# ORD_FV1_1.net
KiCad netlist of a schematic drawn in Altium Designer
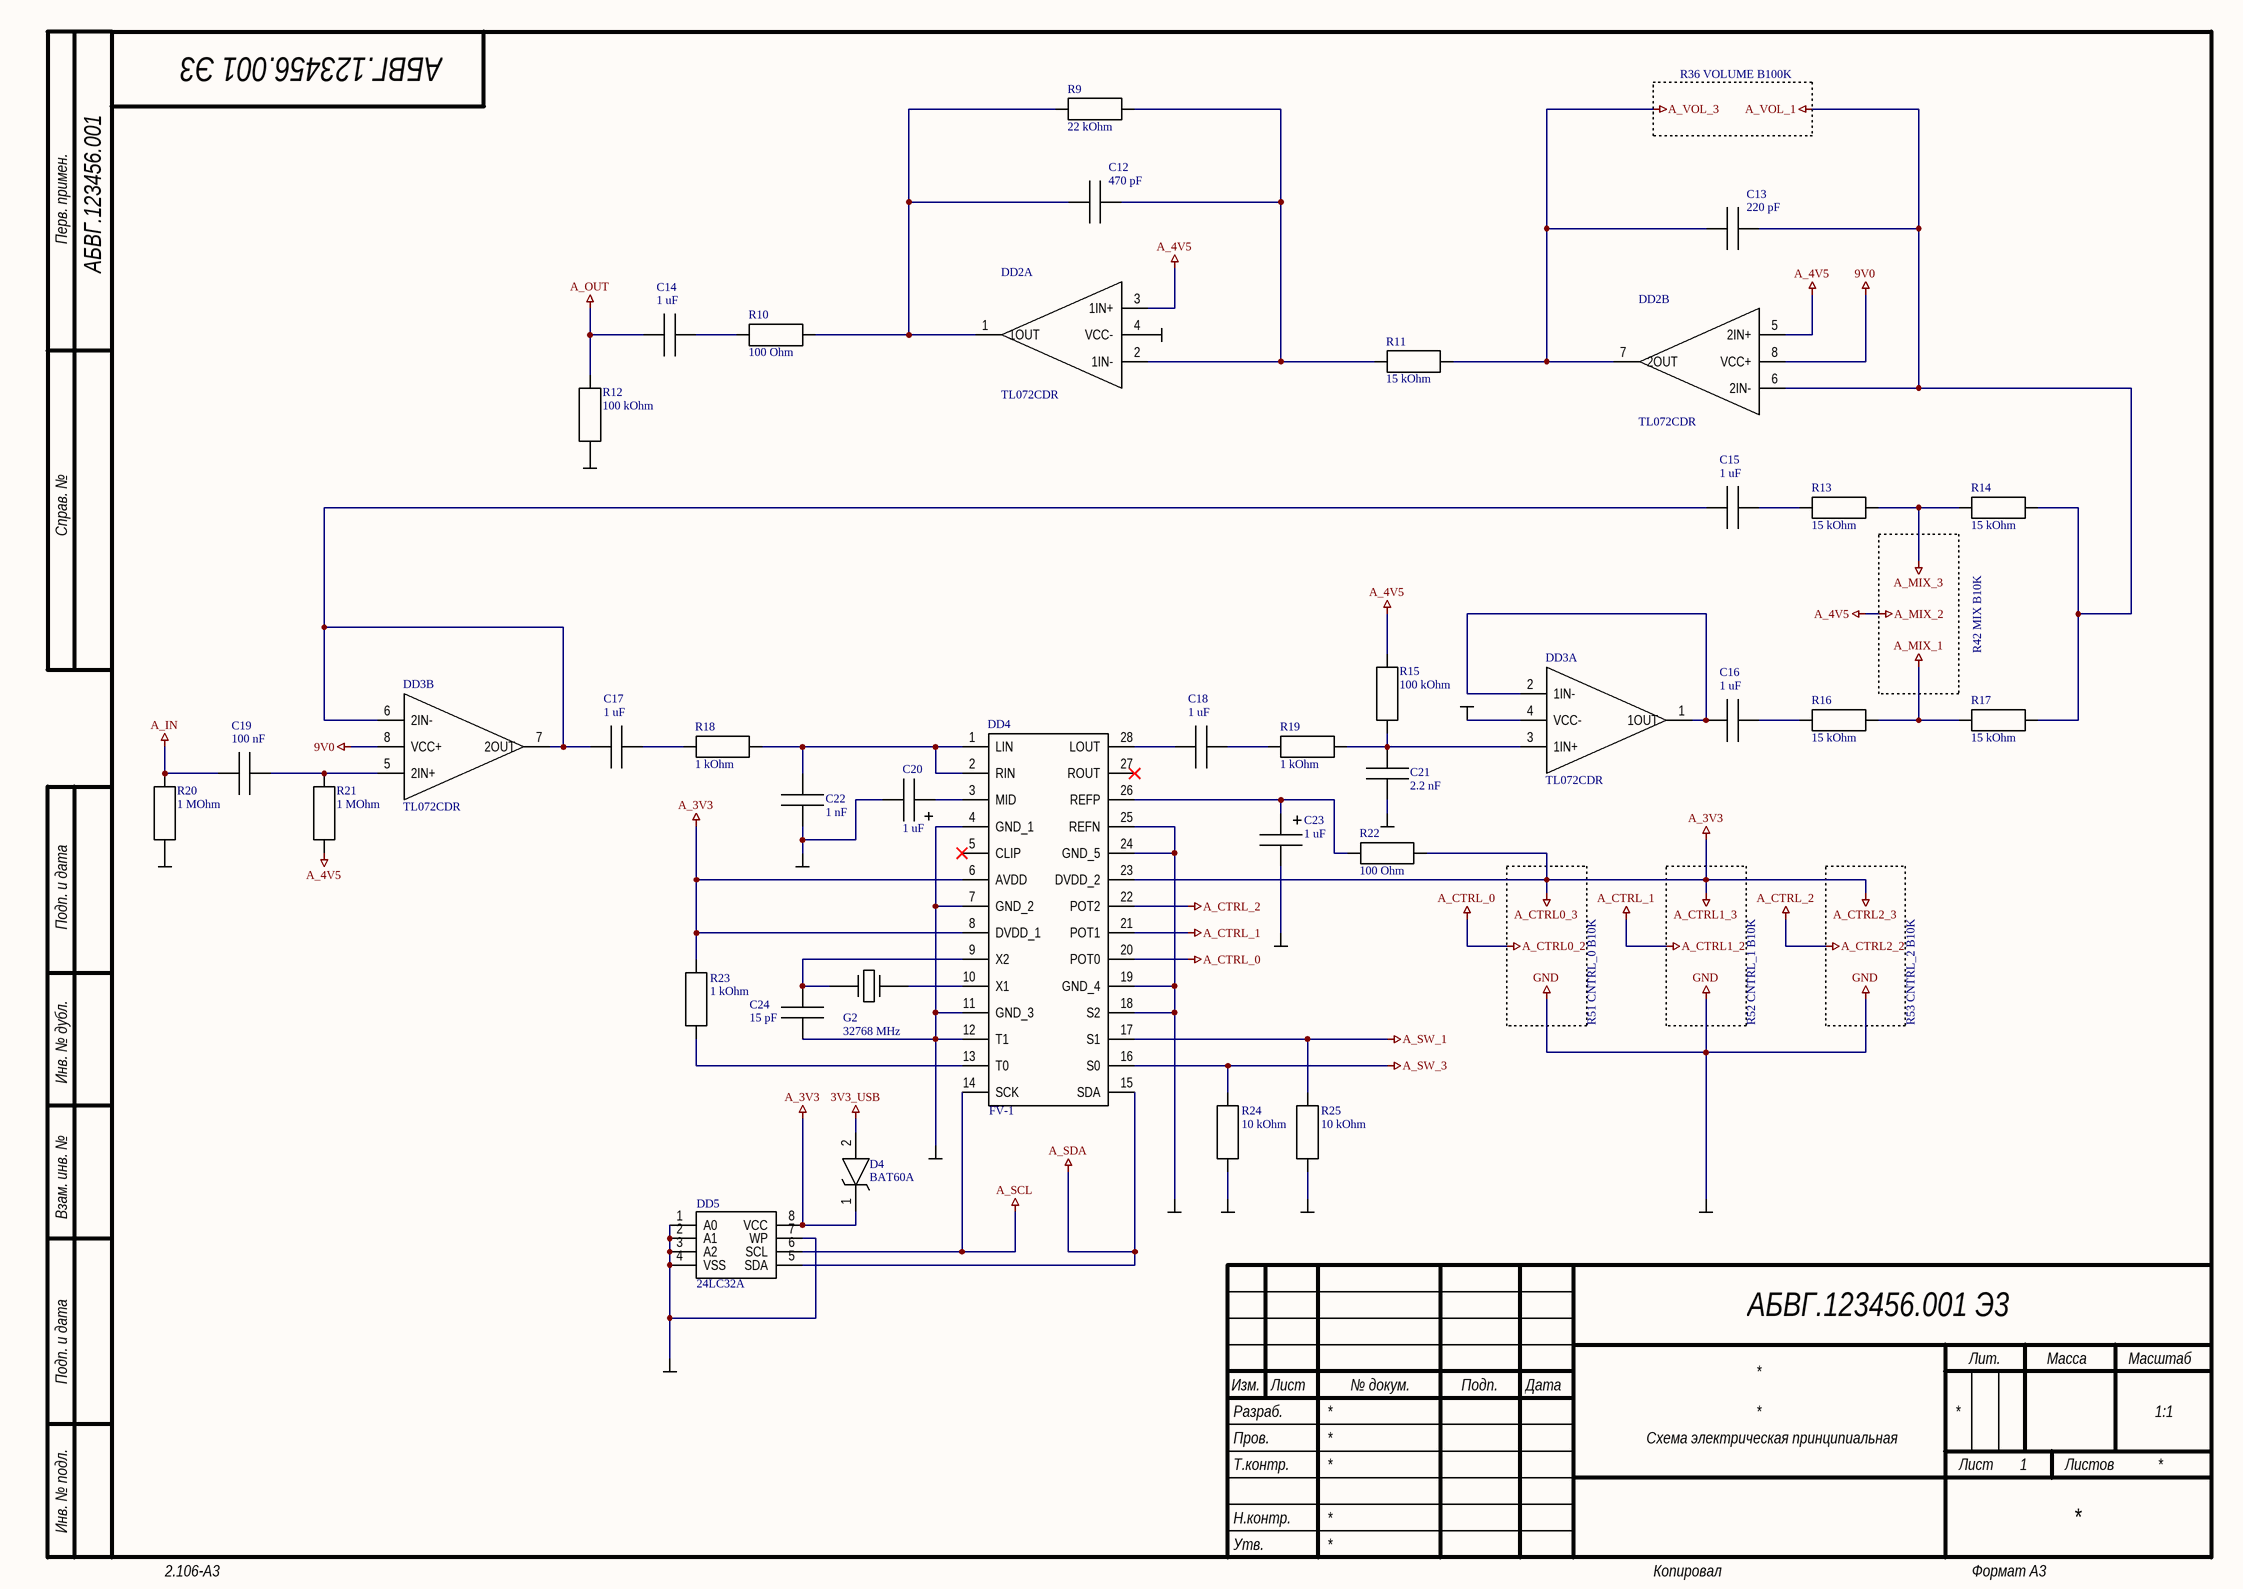
[diagram p0: ORD_FV1_1.SchDoc]

(export (version "E")
  (design (tool "Eeschema 10.0.6"))
  (components
    (comp (ref "C12")
      (value "470 pF")
      (footprint "C0805[2012]")
      (libsource (lib "Gost_passive_lib") (part "Capacitor"))
    )
    (comp (ref "C13")
      (value "220 pF")
      (footprint "C0805[2012]")
      (libsource (lib "Gost_passive_lib") (part "Capacitor"))
    )
    (comp (ref "C14")
      (value "1 uF")
      (footprint "C0805[2012]")
      (libsource (lib "Gost_passive_lib") (part "Capacitor"))
    )
    (comp (ref "C15")
      (value "1 uF")
      (footprint "C0805[2012]")
      (libsource (lib "Gost_passive_lib") (part "Capacitor"))
    )
    (comp (ref "C16")
      (value "1 uF")
      (footprint "C0805[2012]")
      (libsource (lib "Gost_passive_lib") (part "Capacitor"))
    )
    (comp (ref "C17")
      (value "1 uF")
      (footprint "C0805[2012]")
      (libsource (lib "Gost_passive_lib") (part "Capacitor"))
    )
    (comp (ref "C18")
      (value "1 uF")
      (footprint "C0805[2012]")
      (libsource (lib "Gost_passive_lib") (part "Capacitor"))
    )
    (comp (ref "C19")
      (value "100 nF")
      (footprint "C0805[2012]")
      (libsource (lib "Gost_passive_lib") (part "Capacitor"))
    )
    (comp (ref "C20")
      (value "1 uF")
      (footprint "C3216_CASE-A")
      (libsource (lib "Gost_passive_lib") (part "Capacitor_Pol"))
    )
    (comp (ref "C21")
      (value "2.2 nF")
      (footprint "C0805[2012]")
      (libsource (lib "Gost_passive_lib") (part "Capacitor"))
    )
    (comp (ref "C22")
      (value "1 nF")
      (footprint "C0805[2012]")
      (libsource (lib "Gost_passive_lib") (part "Capacitor"))
    )
    (comp (ref "C23")
      (value "1 uF")
      (footprint "C3216_CASE-A")
      (libsource (lib "Gost_passive_lib") (part "Capacitor_Pol"))
    )
    (comp (ref "C24")
      (value "15 pF")
      (footprint "C0805[2012]")
      (libsource (lib "Gost_passive_lib") (part "Capacitor"))
    )
    (comp (ref "D4")
      (value "BAT60A")
      (footprint "SOD323")
      (description "Diode Schottky 10V 3A Automotive 2-Pin SOD-323 T/R")
      (libsource (lib "Gost_passive_lib") (part "BAT60A"))
    )
    (comp (ref "DD2")
      (value "TL072CDR")
      (footprint "SO8")
      (description "TL072CDR, Dual Operational Amplifier 4 MHz -18 to 18V, 8-Pin SO")
      (fields
        (field (name "MANUFACTURER_PART_NUMBER") "LM358DT")
        (field (name "MOUSER PART NUMBER") "511-LM358DT")
      )
      (libsource (lib "Gost_active_libs") (part "TL072CDR"))
    )
    (comp (ref "DD3")
      (value "TL072CDR")
      (footprint "SO8")
      (description "TL072CDR, Dual Operational Amplifier 4 MHz -18 to 18V, 8-Pin SO")
      (fields
        (field (name "MANUFACTURER_PART_NUMBER") "LM358DT")
        (field (name "MOUSER PART NUMBER") "511-LM358DT")
      )
      (libsource (lib "Gost_active_libs") (part "TL072CDR"))
    )
    (comp (ref "DD4")
      (value "FV-1")
      (footprint "SOIC28")
      (description "FV-1 Reverb IC, Integrated Stereo ADC & DAC, Integrated Circuit, SOIC-28 300 MIL")
      (fields (field (name "MANUFACTURER_PART_NUMBER") "FV-1 Reverb IC"))
      (libsource (lib "Gost_active_libs") (part "FV-1"))
    )
    (comp (ref "DD5")
      (value "24LC32A")
      (footprint "DIP8_WITH_SOCKET")
      (description "32K I2C Serial EEPROM with Quarter-Array Write-Protect")
      (fields
        (field (name "MANUFACTURER_PART_NUMBER") "24LC32AF-I/P")
        (field (name "MOUSER PART NUMBER") "579-24LC32AF-I/P")
      )
      (libsource (lib "Gost_active_libs") (part "24LC32A"))
    )
    (comp (ref "G2")
      (value "32768 MHz")
      (footprint "HC-49")
      (libsource (lib "Gost_passive_lib") (part "Crystal_2pin"))
    )
    (comp (ref "R9")
      (value "22 kOhm")
      (footprint "R0805[2012]")
      (libsource (lib "Gost_passive_lib") (part "Resistor"))
    )
    (comp (ref "R10")
      (value "100 Ohm")
      (footprint "R0805[2012]")
      (libsource (lib "Gost_passive_lib") (part "Resistor"))
    )
    (comp (ref "R11")
      (value "15 kOhm")
      (footprint "R0805[2012]")
      (libsource (lib "Gost_passive_lib") (part "Resistor"))
    )
    (comp (ref "R12")
      (value "100 kOhm")
      (footprint "R0805[2012]")
      (libsource (lib "Gost_passive_lib") (part "Resistor"))
    )
    (comp (ref "R13")
      (value "15 kOhm")
      (footprint "R0805[2012]")
      (libsource (lib "Gost_passive_lib") (part "Resistor"))
    )
    (comp (ref "R14")
      (value "15 kOhm")
      (footprint "R0805[2012]")
      (libsource (lib "Gost_passive_lib") (part "Resistor"))
    )
    (comp (ref "R15")
      (value "100 kOhm")
      (footprint "R0805[2012]")
      (libsource (lib "Gost_passive_lib") (part "Resistor"))
    )
    (comp (ref "R16")
      (value "15 kOhm")
      (footprint "R0805[2012]")
      (libsource (lib "Gost_passive_lib") (part "Resistor"))
    )
    (comp (ref "R17")
      (value "15 kOhm")
      (footprint "R0805[2012]")
      (libsource (lib "Gost_passive_lib") (part "Resistor"))
    )
    (comp (ref "R18")
      (value "1 kOhm")
      (footprint "R0805[2012]")
      (libsource (lib "Gost_passive_lib") (part "Resistor"))
    )
    (comp (ref "R19")
      (value "1 kOhm")
      (footprint "R0805[2012]")
      (libsource (lib "Gost_passive_lib") (part "Resistor"))
    )
    (comp (ref "R20")
      (value "1 MOhm")
      (footprint "R0805[2012]")
      (libsource (lib "Gost_passive_lib") (part "Resistor"))
    )
    (comp (ref "R21")
      (value "1 MOhm")
      (footprint "R0805[2012]")
      (libsource (lib "Gost_passive_lib") (part "Resistor"))
    )
    (comp (ref "R22")
      (value "100 Ohm")
      (footprint "R0805[2012]")
      (libsource (lib "Gost_passive_lib") (part "Resistor"))
    )
    (comp (ref "R23")
      (value "1 kOhm")
      (footprint "R0805[2012]")
      (libsource (lib "Gost_passive_lib") (part "Resistor"))
    )
    (comp (ref "R24")
      (value "10 kOhm")
      (footprint "R0805[2012]")
      (libsource (lib "Gost_passive_lib") (part "Resistor"))
    )
    (comp (ref "R25")
      (value "10 kOhm")
      (footprint "R0805[2012]")
      (libsource (lib "Gost_passive_lib") (part "Resistor"))
    )
  )
  (nets
    (net (code "1") (name "3V3_USB") (class "Default")
      (node (ref "D4") (pin "2") (pinfunction "A_2") (pintype "passive"))
    )
    (net (code "2") (name "9V0") (class "Default")
      (node (ref "DD2") (pin "8") (pinfunction "VCC+_8") (pintype "power_in"))
      (node (ref "DD3") (pin "8") (pinfunction "VCC+_8") (pintype "power_in"))
    )
    (net (code "3") (name "A_3V3") (class "Default")
      (node (ref "D4") (pin "1") (pinfunction "K_1") (pintype "passive"))
      (node (ref "DD4") (pin "23") (pinfunction "DVDD_2_23") (pintype "passive"))
      (node (ref "DD4") (pin "6") (pinfunction "AVDD_6") (pintype "passive"))
      (node (ref "DD4") (pin "8") (pinfunction "DVDD_1_8") (pintype "passive"))
      (node (ref "DD5") (pin "8") (pinfunction "VCC_8") (pintype "passive"))
      (node (ref "R22") (pin "1") (pinfunction "1_1") (pintype "passive"))
      (node (ref "R23") (pin "2") (pinfunction "2_2") (pintype "passive"))
    )
    (net (code "4") (name "A_4V5") (class "Default")
      (node (ref "DD2") (pin "3") (pinfunction "1IN+_3") (pintype "passive"))
      (node (ref "DD2") (pin "5") (pinfunction "2IN+_5") (pintype "passive"))
      (node (ref "R15") (pin "1") (pinfunction "1_1") (pintype "passive"))
      (node (ref "R21") (pin "1") (pinfunction "1_1") (pintype "passive"))
    )
    (net (code "5") (name "A_CTRL0_2") (class "Default")
      (node (ref "DD4") (pin "20") (pinfunction "POT0_20") (pintype "passive"))
    )
    (net (code "6") (name "A_CTRL1_2") (class "Default")
      (node (ref "DD4") (pin "21") (pinfunction "POT1_21") (pintype "passive"))
    )
    (net (code "7") (name "A_CTRL2_2") (class "Default")
      (node (ref "DD4") (pin "22") (pinfunction "POT2_22") (pintype "passive"))
    )
    (net (code "8") (name "A_IN") (class "Default")
      (node (ref "C19") (pin "1") (pinfunction "1_1") (pintype "passive"))
      (node (ref "R20") (pin "2") (pinfunction "2_2") (pintype "passive"))
    )
    (net (code "9") (name "A_MIX_1") (class "Default")
      (node (ref "R16") (pin "1") (pinfunction "1_1") (pintype "passive"))
      (node (ref "R17") (pin "2") (pinfunction "2_2") (pintype "passive"))
    )
    (net (code "10") (name "A_MIX_3") (class "Default")
      (node (ref "R13") (pin "1") (pinfunction "1_1") (pintype "passive"))
      (node (ref "R14") (pin "2") (pinfunction "2_2") (pintype "passive"))
    )
    (net (code "11") (name "A_OUT") (class "Default")
      (node (ref "C14") (pin "1") (pinfunction "1_1") (pintype "passive"))
      (node (ref "R12") (pin "2") (pinfunction "2_2") (pintype "passive"))
    )
    (net (code "12") (name "A_SCL") (class "Default")
      (node (ref "DD4") (pin "14") (pinfunction "SCK_14") (pintype "passive"))
      (node (ref "DD5") (pin "6") (pinfunction "SCL_6") (pintype "passive"))
    )
    (net (code "13") (name "A_SDA") (class "Default")
      (node (ref "DD4") (pin "15") (pinfunction "SDA_15") (pintype "passive"))
      (node (ref "DD5") (pin "5") (pinfunction "SDA_5") (pintype "passive"))
    )
    (net (code "14") (name "A_SW_1") (class "Default")
      (node (ref "DD4") (pin "17") (pinfunction "S1_17") (pintype "passive"))
      (node (ref "R25") (pin "2") (pinfunction "2_2") (pintype "passive"))
    )
    (net (code "15") (name "A_SW_3") (class "Default")
      (node (ref "DD4") (pin "16") (pinfunction "S0_16") (pintype "passive"))
      (node (ref "R24") (pin "2") (pinfunction "2_2") (pintype "passive"))
    )
    (net (code "16") (name "A_VOL_1") (class "Default")
      (node (ref "C13") (pin "2") (pinfunction "2_2") (pintype "passive"))
      (node (ref "DD2") (pin "6") (pinfunction "2IN-_6") (pintype "passive"))
      (node (ref "R14") (pin "1") (pinfunction "1_1") (pintype "passive"))
      (node (ref "R17") (pin "1") (pinfunction "1_1") (pintype "passive"))
    )
    (net (code "17") (name "A_VOL_3") (class "Default")
      (node (ref "C13") (pin "1") (pinfunction "1_1") (pintype "passive"))
      (node (ref "DD2") (pin "7") (pinfunction "2OUT_7") (pintype "passive"))
      (node (ref "R11") (pin "1") (pinfunction "1_1") (pintype "passive"))
    )
    (net (code "18") (name "GND") (class "Default")
      (node (ref "C20") (pin "2") (pinfunction "2_2") (pintype "passive"))
      (node (ref "C21") (pin "1") (pinfunction "1_1") (pintype "passive"))
      (node (ref "C22") (pin "1") (pinfunction "1_1") (pintype "passive"))
      (node (ref "C23") (pin "2") (pinfunction "2_2") (pintype "passive"))
      (node (ref "C24") (pin "2") (pinfunction "2_2") (pintype "passive"))
      (node (ref "DD2") (pin "4") (pinfunction "VCC-_4") (pintype "power_in"))
      (node (ref "DD3") (pin "4") (pinfunction "VCC-_4") (pintype "power_in"))
      (node (ref "DD4") (pin "11") (pinfunction "GND_3_11") (pintype "passive"))
      (node (ref "DD4") (pin "12") (pinfunction "T1_12") (pintype "passive"))
      (node (ref "DD4") (pin "18") (pinfunction "S2_18") (pintype "passive"))
      (node (ref "DD4") (pin "19") (pinfunction "GND_4_19") (pintype "passive"))
      (node (ref "DD4") (pin "24") (pinfunction "GND_5_24") (pintype "passive"))
      (node (ref "DD4") (pin "25") (pinfunction "REFN_25") (pintype "passive"))
      (node (ref "DD4") (pin "4") (pinfunction "GND_1_4") (pintype "passive"))
      (node (ref "DD4") (pin "7") (pinfunction "GND_2_7") (pintype "passive"))
      (node (ref "DD5") (pin "1") (pinfunction "A0_1") (pintype "passive"))
      (node (ref "DD5") (pin "2") (pinfunction "A1_2") (pintype "passive"))
      (node (ref "DD5") (pin "3") (pinfunction "A2_3") (pintype "passive"))
      (node (ref "DD5") (pin "4") (pinfunction "VSS_4") (pintype "passive"))
      (node (ref "DD5") (pin "7") (pinfunction "WP_7") (pintype "passive"))
      (node (ref "R12") (pin "1") (pinfunction "1_1") (pintype "passive"))
      (node (ref "R20") (pin "1") (pinfunction "1_1") (pintype "passive"))
      (node (ref "R24") (pin "1") (pinfunction "1_1") (pintype "passive"))
      (node (ref "R25") (pin "1") (pinfunction "1_1") (pintype "passive"))
    )
    (net (code "19") (name "Net-(C14-Pad2)") (class "Default")
      (node (ref "C14") (pin "2") (pinfunction "2_2") (pintype "passive"))
      (node (ref "R10") (pin "2") (pinfunction "2_2") (pintype "passive"))
    )
    (net (code "20") (name "Net-(C15-Pad2)") (class "Default")
      (node (ref "C15") (pin "2") (pinfunction "2_2") (pintype "passive"))
      (node (ref "R13") (pin "2") (pinfunction "2_2") (pintype "passive"))
    )
    (net (code "21") (name "Net-(C16-Pad2)") (class "Default")
      (node (ref "C16") (pin "2") (pinfunction "2_2") (pintype "passive"))
      (node (ref "R16") (pin "2") (pinfunction "2_2") (pintype "passive"))
    )
    (net (code "22") (name "Net-(C17-Pad2)") (class "Default")
      (node (ref "C17") (pin "2") (pinfunction "2_2") (pintype "passive"))
      (node (ref "R18") (pin "2") (pinfunction "2_2") (pintype "passive"))
    )
    (net (code "23") (name "Net-(C18-Pad2)") (class "Default")
      (node (ref "C18") (pin "2") (pinfunction "2_2") (pintype "passive"))
      (node (ref "R19") (pin "2") (pinfunction "2_2") (pintype "passive"))
    )
    (net (code "24") (name "Net-(DD2A-1IN-)") (class "Default")
      (node (ref "C12") (pin "2") (pinfunction "2_2") (pintype "passive"))
      (node (ref "DD2") (pin "2") (pinfunction "1IN-_2") (pintype "passive"))
      (node (ref "R11") (pin "2") (pinfunction "2_2") (pintype "passive"))
      (node (ref "R9") (pin "1") (pinfunction "1_1") (pintype "passive"))
    )
    (net (code "25") (name "Net-(DD2A-1OUT)") (class "Default")
      (node (ref "C12") (pin "1") (pinfunction "1_1") (pintype "passive"))
      (node (ref "DD2") (pin "1") (pinfunction "1OUT_1") (pintype "passive"))
      (node (ref "R10") (pin "1") (pinfunction "1_1") (pintype "passive"))
      (node (ref "R9") (pin "2") (pinfunction "2_2") (pintype "passive"))
    )
    (net (code "26") (name "Net-(DD3A-1IN+)") (class "Default")
      (node (ref "C21") (pin "2") (pinfunction "2_2") (pintype "passive"))
      (node (ref "DD3") (pin "3") (pinfunction "1IN+_3") (pintype "passive"))
      (node (ref "R15") (pin "2") (pinfunction "2_2") (pintype "passive"))
      (node (ref "R19") (pin "1") (pinfunction "1_1") (pintype "passive"))
    )
    (net (code "27") (name "Net-(DD3A-1IN-)") (class "Default")
      (node (ref "C16") (pin "1") (pinfunction "1_1") (pintype "passive"))
      (node (ref "DD3") (pin "1") (pinfunction "1OUT_1") (pintype "passive"))
      (node (ref "DD3") (pin "2") (pinfunction "1IN-_2") (pintype "passive"))
    )
    (net (code "28") (name "Net-(DD3B-2IN+)") (class "Default")
      (node (ref "C19") (pin "2") (pinfunction "2_2") (pintype "passive"))
      (node (ref "DD3") (pin "5") (pinfunction "2IN+_5") (pintype "passive"))
      (node (ref "R21") (pin "2") (pinfunction "2_2") (pintype "passive"))
    )
    (net (code "29") (name "Net-(DD3B-2IN-)") (class "Default")
      (node (ref "C15") (pin "1") (pinfunction "1_1") (pintype "passive"))
      (node (ref "C17") (pin "1") (pinfunction "1_1") (pintype "passive"))
      (node (ref "DD3") (pin "6") (pinfunction "2IN-_6") (pintype "passive"))
      (node (ref "DD3") (pin "7") (pinfunction "2OUT_7") (pintype "passive"))
    )
    (net (code "30") (name "Net-(DD4-LIN)") (class "Default")
      (node (ref "C22") (pin "2") (pinfunction "2_2") (pintype "passive"))
      (node (ref "DD4") (pin "1") (pinfunction "LIN_1") (pintype "passive"))
      (node (ref "DD4") (pin "2") (pinfunction "RIN_2") (pintype "passive"))
      (node (ref "R18") (pin "1") (pinfunction "1_1") (pintype "passive"))
    )
    (net (code "31") (name "Net-(DD4-LOUT)") (class "Default")
      (node (ref "C18") (pin "1") (pinfunction "1_1") (pintype "passive"))
      (node (ref "DD4") (pin "28") (pinfunction "LOUT_28") (pintype "passive"))
    )
    (net (code "32") (name "Net-(DD4-MID)") (class "Default")
      (node (ref "C20") (pin "1") (pinfunction "1_1") (pintype "passive"))
      (node (ref "DD4") (pin "3") (pinfunction "MID_3") (pintype "passive"))
    )
    (net (code "33") (name "Net-(DD4-REFP)") (class "Default")
      (node (ref "C23") (pin "1") (pinfunction "1_1") (pintype "passive"))
      (node (ref "DD4") (pin "26") (pinfunction "REFP_26") (pintype "passive"))
      (node (ref "R22") (pin "2") (pinfunction "2_2") (pintype "passive"))
    )
    (net (code "34") (name "Net-(DD4-T0)") (class "Default")
      (node (ref "DD4") (pin "13") (pinfunction "T0_13") (pintype "passive"))
      (node (ref "R23") (pin "1") (pinfunction "1_1") (pintype "passive"))
    )
    (net (code "35") (name "Net-(DD4-X1)") (class "Default")
      (node (ref "DD4") (pin "10") (pinfunction "X1_10") (pintype "passive"))
      (node (ref "G2") (pin "2") (pinfunction "2_2") (pintype "passive"))
    )
    (net (code "36") (name "Net-(DD4-X2)") (class "Default")
      (node (ref "C24") (pin "1") (pinfunction "1_1") (pintype "passive"))
      (node (ref "DD4") (pin "9") (pinfunction "X2_9") (pintype "passive"))
      (node (ref "G2") (pin "1") (pinfunction "1_1") (pintype "passive"))
    )
    (net (code "37") (name "unconnected-(DD4-CLIP-Pad5)") (class "Default")
      (node (ref "DD4") (pin "5") (pinfunction "CLIP_5") (pintype "passive+no_connect"))
    )
    (net (code "38") (name "unconnected-(DD4-ROUT-Pad27)") (class "Default")
      (node (ref "DD4") (pin "27") (pinfunction "ROUT_27") (pintype "passive+no_connect"))
    )
  )
)
